# INPUT_PROTECTION.net
KiCad netlist of a schematic drawn in Altium Designer
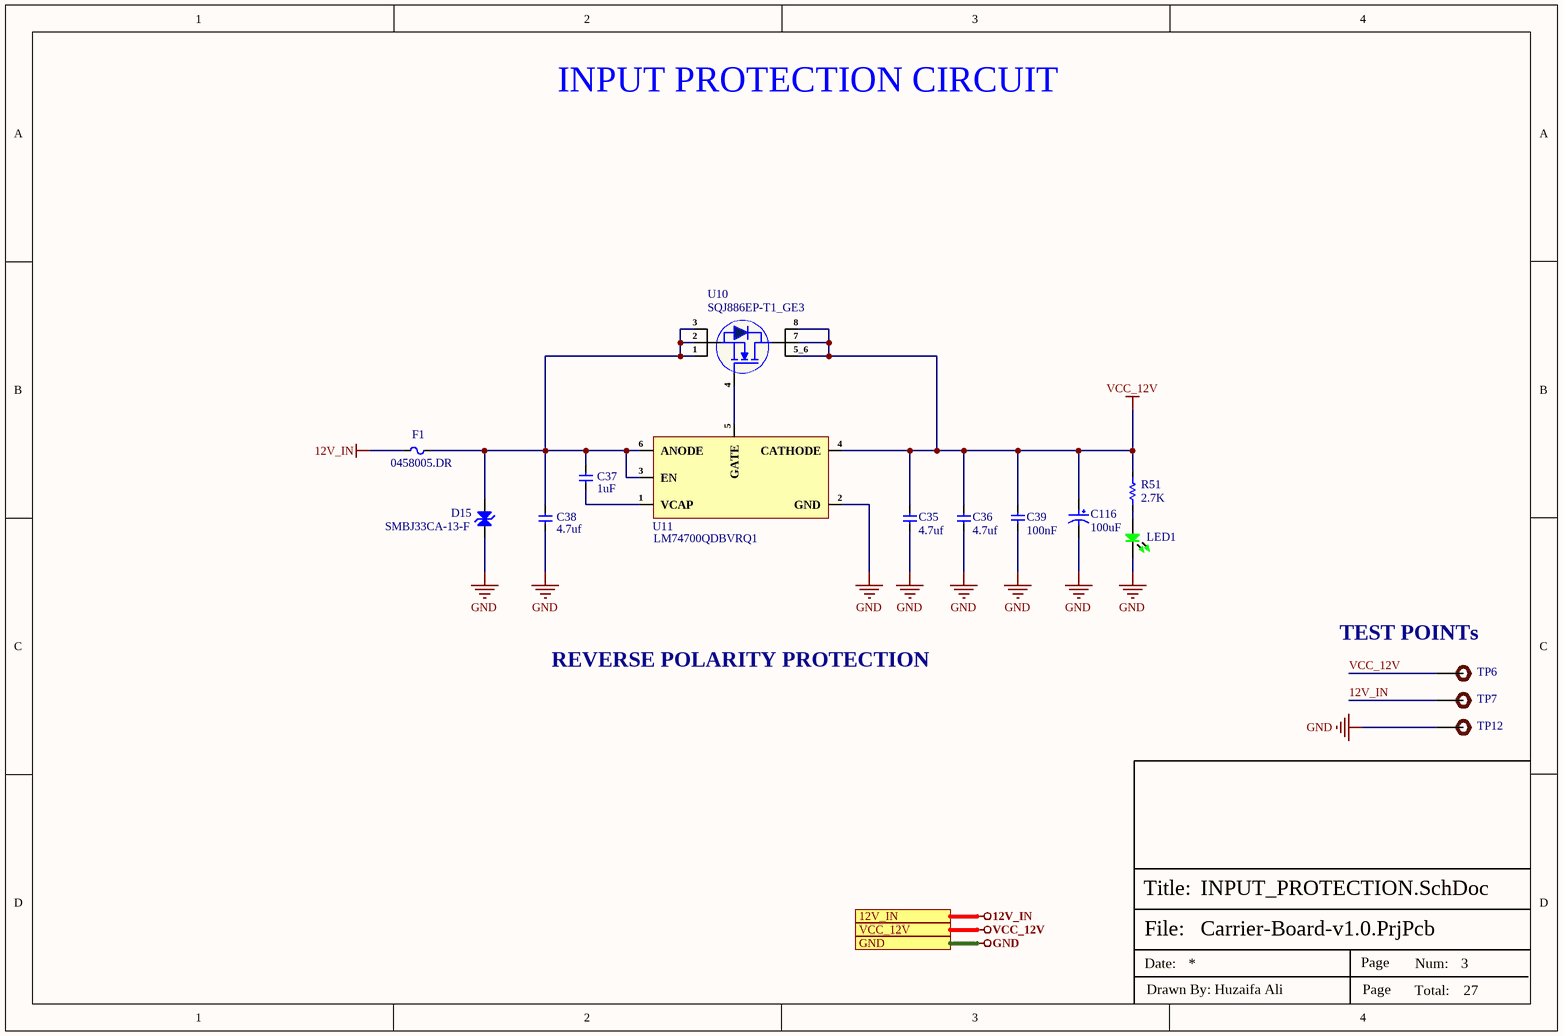
[diagram p0: INPUT_PROTECTION.SchDoc]

(export (version "E")
  (design (tool "Eeschema 10.0.6"))
  (components
    (comp (ref "C35")
      (value "4.7uf")
      (footprint "Cap-0805")
      (description "CAP CER 4.7UF 50V X5R 0805")
      (fields
        (field (name "MANUFACTURER") "Murata")
        (field (name "MANUFACTURER PART NUMBER") "GRM21BR61H475KE51L")
      )
      (libsource (lib "eSpark Libraries") (part "GRM21BR61H475KE51L"))
    )
    (comp (ref "C36")
      (value "4.7uf")
      (footprint "Cap-0805")
      (description "CAP CER 4.7UF 50V X5R 0805")
      (fields
        (field (name "MANUFACTURER") "Murata")
        (field (name "MANUFACTURER PART NUMBER") "GRM21BR61H475KE51L")
      )
      (libsource (lib "eSpark Libraries") (part "GRM21BR61H475KE51L"))
    )
    (comp (ref "C37")
      (value "1uF")
      (footprint "Cap-0402")
      (description "CAP CER 1UF 25V X5R 0402")
      (fields
        (field (name "MANUFACTURER") "Yageo")
        (field (name "MANUFACTURER PART NUMBER") "CC0402KRX5R8BB105")
      )
      (libsource (lib "eSpark Libraries") (part "CC0402KRX5R8BB105"))
    )
    (comp (ref "C38")
      (value "4.7uf")
      (footprint "Cap-0805")
      (description "CAP CER 4.7UF 50V X5R 0805")
      (fields
        (field (name "MANUFACTURER") "Murata")
        (field (name "MANUFACTURER PART NUMBER") "GRM21BR61H475KE51L")
      )
      (libsource (lib "eSpark Libraries") (part "GRM21BR61H475KE51L"))
    )
    (comp (ref "C39")
      (value "100nF")
      (footprint "cap-0402")
      (description "CAP CER 0.1UF 50V X7R 0402")
      (fields
        (field (name "MANUFACTURER") "TDK")
        (field (name "MANUFACTURER PART NUMBER") "C1005X7R1H104KT000F")
      )
      (libsource (lib "eSpark Libraries") (part "C1005X7R1H104KT000F"))
    )
    (comp (ref "C116")
      (value "100uF")
      (footprint "RVT1H101M0607")
      (description "100uF 50V ±20% SMD,D6.3xL7.7mm Aluminum Electrolytic Capacitors - SMD ROHS")
      (fields
        (field (name "MANUFACTURER") "ROQANG")
        (field (name "MANUFACTURER PART NUMBER") "RVT1H101M0607")
      )
      (libsource (lib "eSpark Libraries") (part "RVT1H101M0607"))
    )
    (comp (ref "D15")
      (value "SMBJ33CA-13-F")
      (footprint "SMB Bi Directional")
      (description "TVS DIODE 33VWM 53.3VC SMB")
      (fields (field (name "MANUFACTURER") "Diodes") (field (name "LCSC PART NUMBER") "C135068"))
      (libsource (lib "eSpark Libraries") (part "SMBJ33CA-13-F"))
    )
    (comp (ref "F1")
      (value "0458005.DR")
      (footprint "Fuse 1206 (3216 Metric)")
      (description "FUSE BRD MNT 5A 32VAC 75VDC 1206")
      (fields (field (name "MANUFACTURER") "Littelfuse") (field (name "LCSC PART NUMBER") "C187561"))
      (libsource (lib "eSpark Libraries") (part "0458005.DR"))
    )
    (comp (ref "LED1")
      (value "~")
      (footprint "LED-0603")
      (description "Emerald 0603 Light Emitting Diodes (LED) ROHS")
      (fields
        (field (name "MANUFACTURER") "Foshan NationStar Optoelectronics")
        (field (name "MANUFACTURER PART NUMBER") "NCD0603G2")
      )
      (libsource (lib "eSpark Libraries") (part "NCD0603G2"))
    )
    (comp (ref "R51")
      (value "2.7K")
      (footprint "Res-0603")
      (description "RES 2.7K OHM 1% 1/10W 0603")
      (fields
        (field (name "MANUFACTURER") "Yageo")
        (field (name "MANUFACTURER PART NUMBER") "RC0603FR-072K7L")
      )
      (libsource (lib "eSpark Libraries") (part "RC0603FR-072K7L"))
    )
    (comp (ref "TP6")
      (value "TEST POINT 0.5mm Dia")
      (footprint "Test-point - 0.5mm")
      (description "Test Point ON")
      (libsource (lib "eSpark Libraries") (part "TEST POINT 0.5mm Dia"))
    )
    (comp (ref "TP7")
      (value "TEST POINT 0.5mm Dia")
      (footprint "Test-point - 0.5mm")
      (description "Test Point ON")
      (libsource (lib "eSpark Libraries") (part "TEST POINT 0.5mm Dia"))
    )
    (comp (ref "TP12")
      (value "TEST POINT 0.5mm Dia")
      (footprint "Test-point - 0.5mm")
      (description "Test Point ON")
      (libsource (lib "eSpark Libraries") (part "TEST POINT 0.5mm Dia"))
    )
    (comp (ref "U10")
      (value "SQJ886EP-T1_GE3")
      (footprint "PowerPAK-SO-8")
      (description "MOSFET N-CH 40V 60A PPAK SO-8")
      (fields (field (name "MANUFACTURER") "Vishay Siliconix") (field (name "LCSC PART NUMBER") "C727822"))
      (libsource (lib "eSpark Libraries") (part "SQJ886EP-T1_GE3"))
    )
    (comp (ref "U11")
      (value "LM74700QDBVRQ1")
      (footprint "SOT-23-6")
      (description "OR Controller N+1 ORing Controller N-Channel 1:1 SOT-23-6")
      (fields (field (name "MANUFACTURER") "Texas Instruments") (field (name "LCSC PART NUMBER") "C2941042"))
      (libsource (lib "eSpark Libraries") (part "LM74700QDBVRQ1"))
    )
  )
  (nets
    (net (code "1") (name "12V_IN") (class "Default")
      (node (ref "F1") (pin "2") (pinfunction "2_2") (pintype "passive"))
      (node (ref "TP7") (pin "1") (pinfunction "1_1") (pintype "passive"))
    )
    (net (code "2") (name "GND") (class "Default")
      (node (ref "C116") (pin "2") (pintype "passive"))
      (node (ref "C35") (pin "1") (pinfunction "1_1") (pintype "passive"))
      (node (ref "C36") (pin "1") (pinfunction "1_1") (pintype "passive"))
      (node (ref "C38") (pin "1") (pinfunction "1_1") (pintype "passive"))
      (node (ref "C39") (pin "2") (pinfunction "2_2") (pintype "passive"))
      (node (ref "D15") (pin "1") (pinfunction "A_1") (pintype "passive"))
      (node (ref "LED1") (pin "2") (pinfunction "2_2") (pintype "passive"))
      (node (ref "TP12") (pin "1") (pinfunction "1_1") (pintype "passive"))
      (node (ref "U11") (pin "2") (pinfunction "GND_2") (pintype "passive"))
    )
    (net (code "3") (name "Net-(D15-K)") (class "Default")
      (node (ref "C37") (pin "2") (pinfunction "2_2") (pintype "passive"))
      (node (ref "C38") (pin "2") (pinfunction "2_2") (pintype "passive"))
      (node (ref "D15") (pin "2") (pinfunction "K_2") (pintype "passive"))
      (node (ref "F1") (pin "1") (pinfunction "1_1") (pintype "passive"))
      (node (ref "U10") (pin "1") (pinfunction "S_1") (pintype "passive"))
      (node (ref "U10") (pin "2") (pinfunction "S_2") (pintype "passive"))
      (node (ref "U10") (pin "3") (pinfunction "S_3") (pintype "passive"))
      (node (ref "U11") (pin "3") (pinfunction "EN_3") (pintype "passive"))
      (node (ref "U11") (pin "6") (pinfunction "ANODE_6") (pintype "passive"))
    )
    (net (code "4") (name "Net-(LED1-Pad1)") (class "Default")
      (node (ref "LED1") (pin "1") (pinfunction "1_1") (pintype "passive"))
      (node (ref "R51") (pin "2") (pinfunction "2_2") (pintype "passive"))
    )
    (net (code "5") (name "Net-(U10-G)") (class "Default")
      (node (ref "U10") (pin "4") (pinfunction "G_4") (pintype "passive"))
      (node (ref "U11") (pin "5") (pinfunction "GATE_5") (pintype "passive"))
    )
    (net (code "6") (name "Net-(U11-VCAP)") (class "Default")
      (node (ref "C37") (pin "1") (pinfunction "1_1") (pintype "passive"))
      (node (ref "U11") (pin "1") (pinfunction "VCAP_1") (pintype "passive"))
    )
    (net (code "7") (name "VCC_12V") (class "Default")
      (node (ref "C116") (pin "1") (pintype "passive"))
      (node (ref "C35") (pin "2") (pinfunction "2_2") (pintype "passive"))
      (node (ref "C36") (pin "2") (pinfunction "2_2") (pintype "passive"))
      (node (ref "C39") (pin "1") (pinfunction "1_1") (pintype "passive"))
      (node (ref "R51") (pin "1") (pinfunction "1_1") (pintype "passive"))
      (node (ref "TP6") (pin "1") (pinfunction "1_1") (pintype "passive"))
      (node (ref "U10") (pin "5_6") (pinfunction "D_5_6") (pintype "passive"))
      (node (ref "U10") (pin "7") (pinfunction "D_7") (pintype "passive"))
      (node (ref "U10") (pin "8") (pinfunction "D_8") (pintype "passive"))
      (node (ref "U11") (pin "4") (pinfunction "CATHODE_4") (pintype "passive"))
    )
  )
)
